# BoneConductionAmp.net
KiCad netlist of a schematic drawn in EAGLE
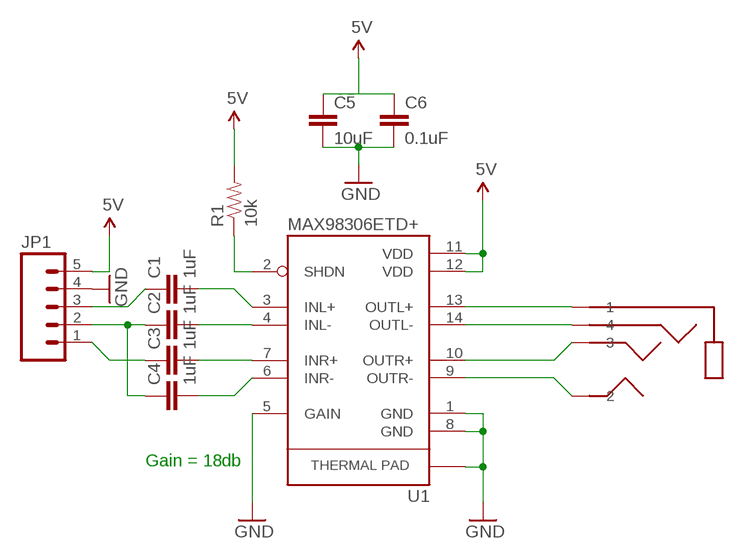
[diagram p0: schematic, sheet 1]

(export (version "E")
  (design (tool "Eeschema 10.0.6"))
  (components
    (comp (ref "C1")
      (value "1uF")
      (footprint "eagle-import:0402-CAP")
      (libsource (lib "eagle-import") (part "CAP0402-CAP"))
    )
    (comp (ref "C2")
      (value "1uF")
      (footprint "eagle-import:0402-CAP")
      (libsource (lib "eagle-import") (part "CAP0402-CAP"))
    )
    (comp (ref "C3")
      (value "1uF")
      (footprint "eagle-import:0402-CAP")
      (libsource (lib "eagle-import") (part "CAP0402-CAP"))
    )
    (comp (ref "C4")
      (value "1uF")
      (footprint "eagle-import:0402-CAP")
      (libsource (lib "eagle-import") (part "CAP0402-CAP"))
    )
    (comp (ref "C5")
      (value "10uF")
      (footprint "eagle-import:0805")
      (libsource (lib "eagle-import") (part "CAP0805"))
    )
    (comp (ref "C6")
      (value "0.1uF")
      (footprint "eagle-import:0402-CAP")
      (libsource (lib "eagle-import") (part "CAP0402-CAP"))
    )
    (comp (ref "JP1")
      (value "M05PTH")
      (footprint "eagle-import:1X05")
      (libsource (lib "eagle-import") (part "M05PTH"))
    )
    (comp (ref "R1")
      (value "10k")
      (footprint "eagle-import:0603-RES")
      (libsource (lib "eagle-import") (part "RESISTOR0603-RES"))
    )
    (comp (ref "U$4")
      (value "TRRS-2.5MM-FEMALE4-CON")
      (footprint "eagle-import:TRRS-2.5MM-JACK-SMD")
      (libsource (lib "eagle-import") (part "TRRS-2.5MM-FEMALE4-CON"))
    )
    (comp (ref "U1")
      (value "MAX98306ETD+")
      (footprint "eagle-import:14-TDFN")
      (libsource (lib "eagle-import") (part "MAX98306ETD+"))
    )
  )
  (nets
    (net (code "1") (name "5V") (class "Default")
      (node (ref "C5") (pin "1") (pinfunction "1_1") (pintype "passive"))
      (node (ref "C6") (pin "1") (pinfunction "1_1") (pintype "passive"))
      (node (ref "JP1") (pin "5") (pinfunction "5_5") (pintype "passive"))
      (node (ref "R1") (pin "2") (pinfunction "2_2") (pintype "passive"))
      (node (ref "U1") (pin "11") (pinfunction "VDD_11") (pintype "power_in"))
      (node (ref "U1") (pin "12") (pinfunction "VDD_12") (pintype "power_in"))
    )
    (net (code "2") (name "GND") (class "Default")
      (node (ref "C5") (pin "2") (pinfunction "2_2") (pintype "passive"))
      (node (ref "C6") (pin "2") (pinfunction "2_2") (pintype "passive"))
      (node (ref "JP1") (pin "4") (pinfunction "4_4") (pintype "passive"))
      (node (ref "U1") (pin "1") (pinfunction "GND_1") (pintype "power_in"))
      (node (ref "U1") (pin "15") (pinfunction "GND_15") (pintype "power_in"))
      (node (ref "U1") (pin "5") (pinfunction "GAIN_5") (pintype "passive"))
      (node (ref "U1") (pin "8") (pinfunction "GND_8") (pintype "power_in"))
    )
    (net (code "3") (name "Net-(C1-Pad1)") (class "Default")
      (node (ref "C1") (pin "1") (pinfunction "1_1") (pintype "passive"))
      (node (ref "JP1") (pin "3") (pinfunction "3_3") (pintype "passive"))
    )
    (net (code "4") (name "Net-(C2-Pad1)") (class "Default")
      (node (ref "C2") (pin "1") (pinfunction "1_1") (pintype "passive"))
      (node (ref "C4") (pin "1") (pinfunction "1_1") (pintype "passive"))
      (node (ref "JP1") (pin "2") (pinfunction "2_2") (pintype "passive"))
    )
    (net (code "5") (name "Net-(C3-Pad1)") (class "Default")
      (node (ref "C3") (pin "1") (pinfunction "1_1") (pintype "passive"))
      (node (ref "JP1") (pin "1") (pinfunction "1_1") (pintype "passive"))
    )
    (net (code "6") (name "Net-(U$4-1)") (class "Default")
      (node (ref "U$4") (pin "P1") (pinfunction "1_P1") (pintype "bidirectional"))
      (node (ref "U1") (pin "13") (pinfunction "OUTL+_13") (pintype "bidirectional"))
    )
    (net (code "7") (name "Net-(U$4-2)") (class "Default")
      (node (ref "U$4") (pin "P2") (pinfunction "2_P2") (pintype "bidirectional"))
      (node (ref "U1") (pin "9") (pinfunction "OUTR-_9") (pintype "bidirectional"))
    )
    (net (code "8") (name "Net-(U$4-3)") (class "Default")
      (node (ref "U$4") (pin "P3") (pinfunction "3_P3") (pintype "bidirectional"))
      (node (ref "U1") (pin "10") (pinfunction "OUTR+_10") (pintype "bidirectional"))
    )
    (net (code "9") (name "Net-(U1-INL+)") (class "Default")
      (node (ref "C1") (pin "2") (pinfunction "2_2") (pintype "passive"))
      (node (ref "U1") (pin "3") (pinfunction "INL+_3") (pintype "bidirectional"))
    )
    (net (code "10") (name "Net-(U1-INL-)") (class "Default")
      (node (ref "C2") (pin "2") (pinfunction "2_2") (pintype "passive"))
      (node (ref "U1") (pin "4") (pinfunction "INL-_4") (pintype "bidirectional"))
    )
    (net (code "11") (name "Net-(U1-INR+)") (class "Default")
      (node (ref "C3") (pin "2") (pinfunction "2_2") (pintype "passive"))
      (node (ref "U1") (pin "7") (pinfunction "INR+_7") (pintype "bidirectional"))
    )
    (net (code "12") (name "Net-(U1-INR-)") (class "Default")
      (node (ref "C4") (pin "2") (pinfunction "2_2") (pintype "passive"))
      (node (ref "U1") (pin "6") (pinfunction "INR-_6") (pintype "bidirectional"))
    )
    (net (code "13") (name "Net-(U1-OUTL-)") (class "Default")
      (node (ref "U$4") (pin "P4") (pinfunction "4_P4") (pintype "bidirectional"))
      (node (ref "U$4") (pin "P4.1") (pinfunction "4_P4.1") (pintype "bidirectional"))
      (node (ref "U1") (pin "14") (pinfunction "OUTL-_14") (pintype "bidirectional"))
    )
    (net (code "14") (name "Net-(U1-SHDN)") (class "Default")
      (node (ref "R1") (pin "1") (pinfunction "1_1") (pintype "passive"))
      (node (ref "U1") (pin "2") (pinfunction "SHDN_2") (pintype "input"))
    )
  )
)
